# POWER.net
KiCad netlist of a schematic drawn in Altium Designer
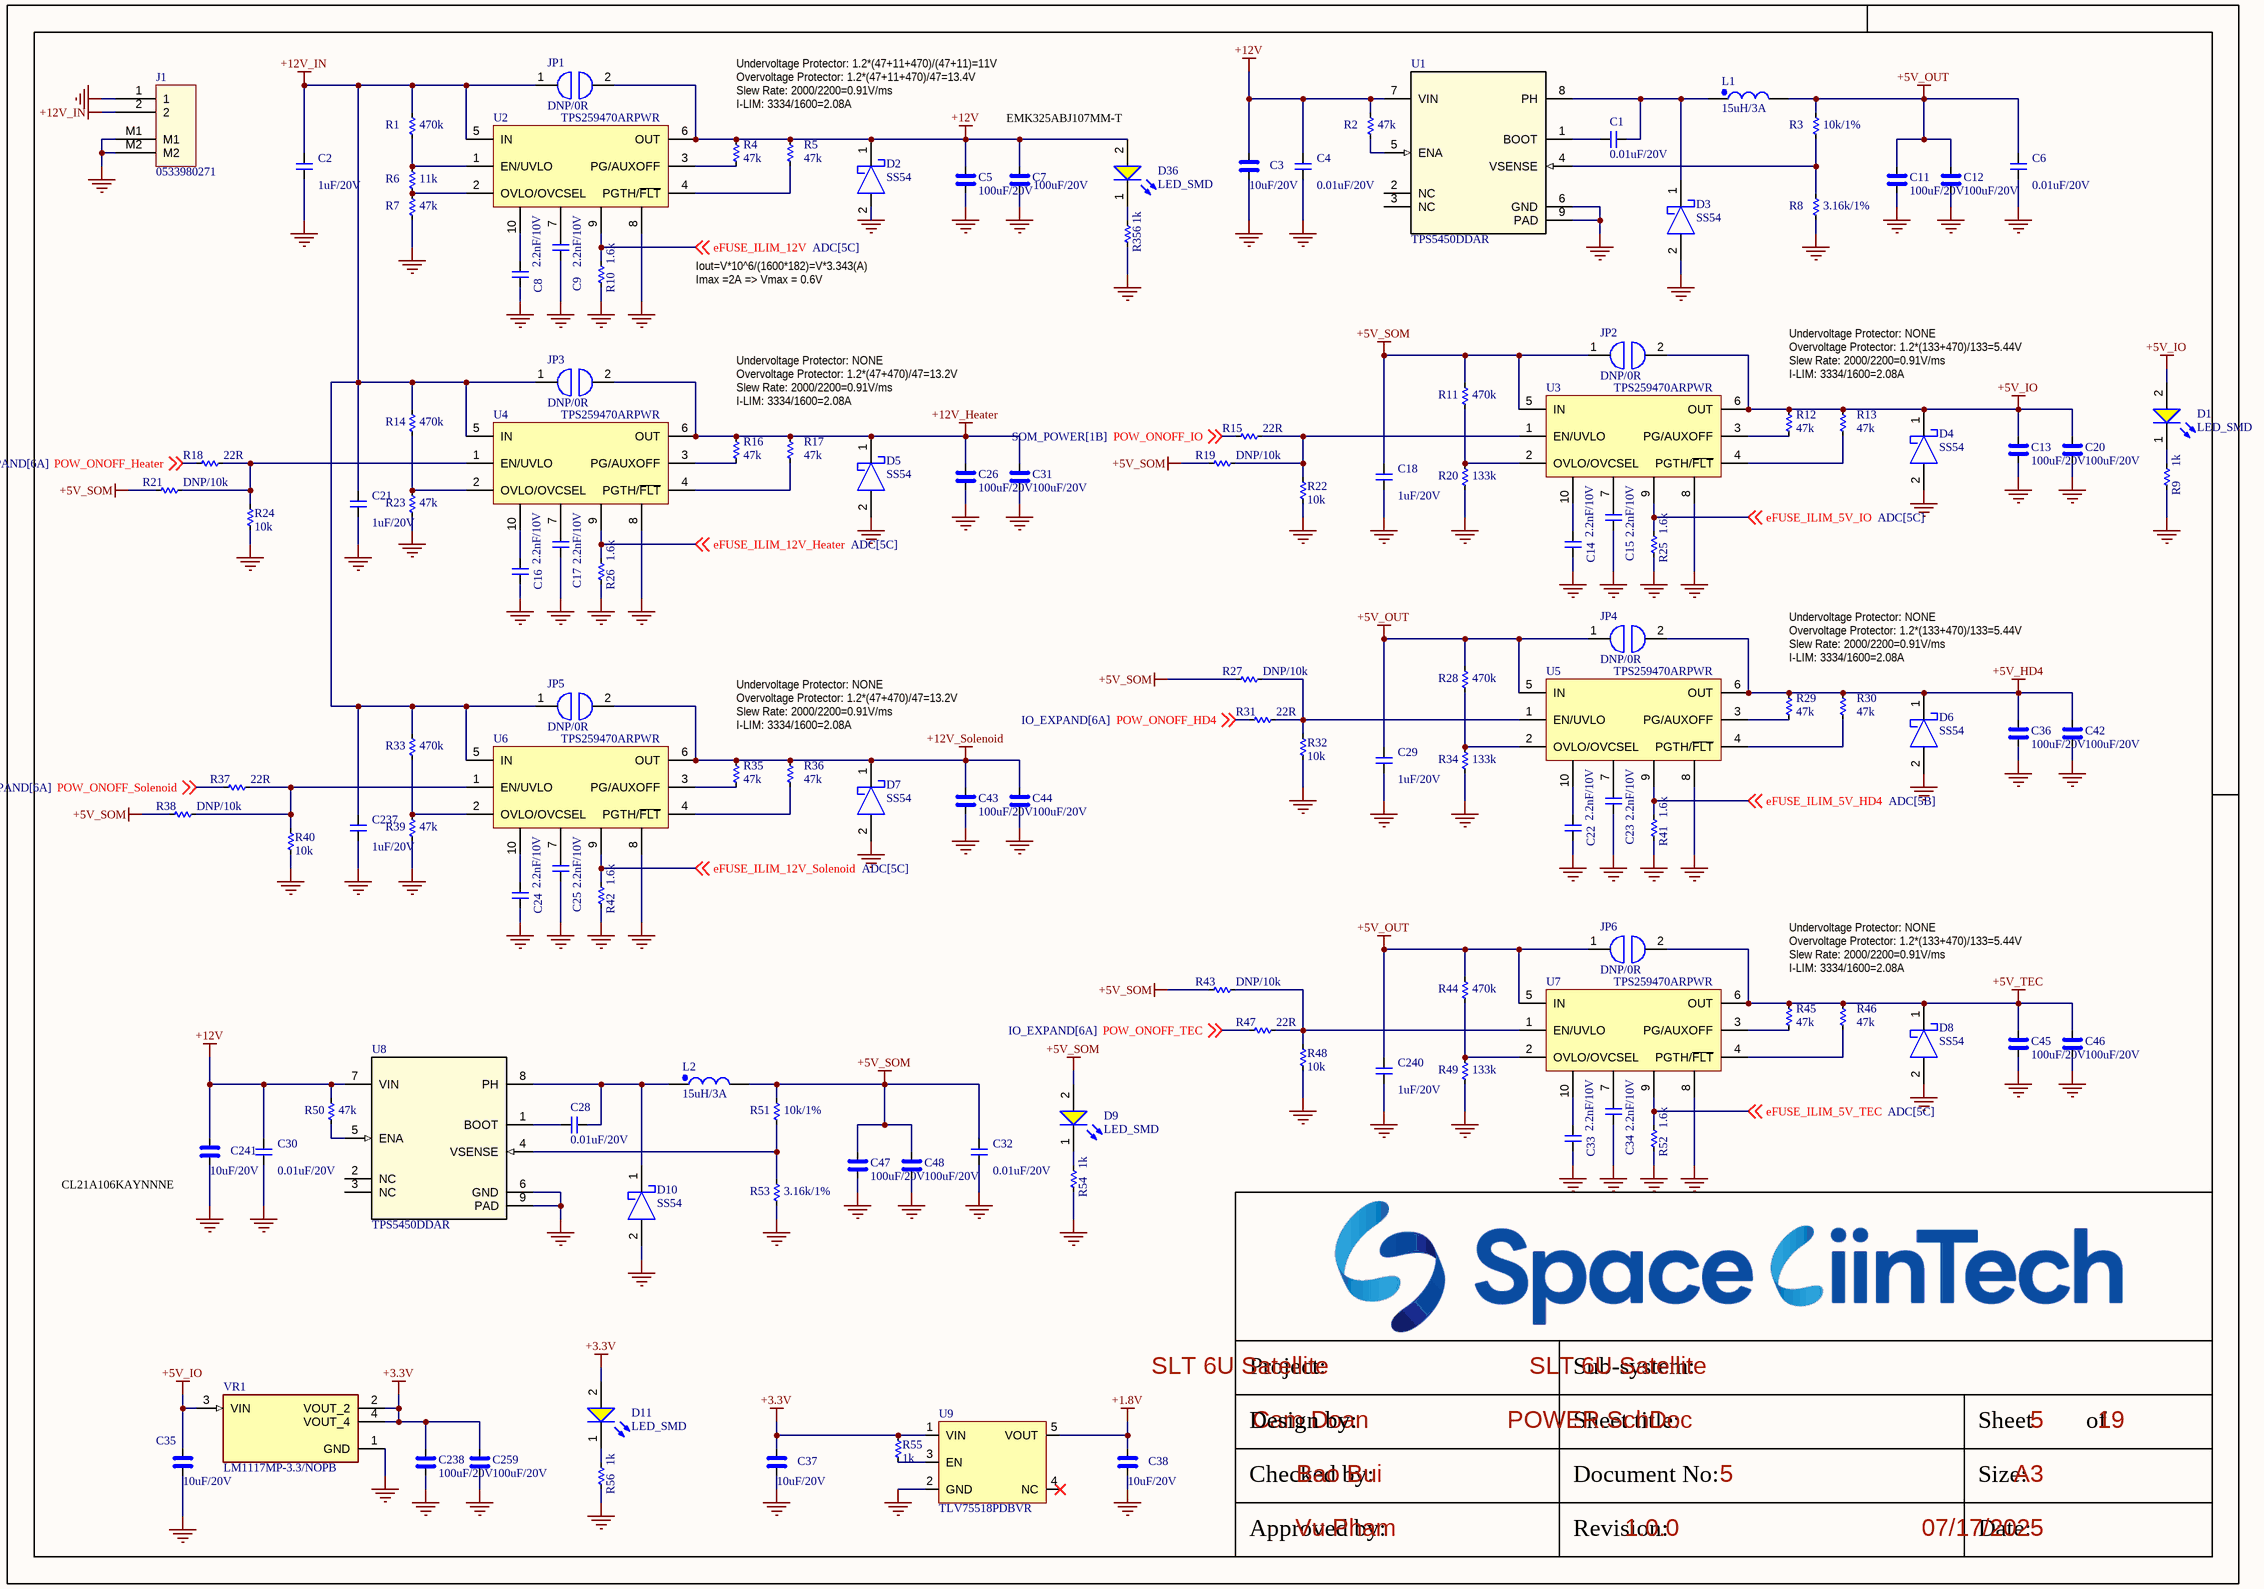
[diagram p0: POWER.SchDoc]

(export (version "E")
  (design (tool "Eeschema 10.0.6"))
  (components
    (comp (ref "C1")
      (value "0.01uF/20V")
      (footprint "CAP_C_1005X60")
      (description "CAP CHIP")
      (libsource (lib "LABLIB") (part "_CAP_C_2"))
    )
    (comp (ref "C2")
      (value "1uF/20V")
      (footprint "CAP_C_1005X60")
      (description "CAP CHIP")
      (libsource (lib "LABLIB") (part "_CAP_C_2"))
    )
    (comp (ref "C3")
      (value "10uF/20V")
      (footprint "CAP_C_2012X110")
      (description "CAP CHIP High Value")
      (libsource (lib "LABLIB") (part "_CAP_C_High_2"))
    )
    (comp (ref "C4")
      (value "0.01uF/20V")
      (footprint "CAP_C_1005X60")
      (description "CAP CHIP")
      (libsource (lib "LABLIB") (part "_CAP_C_2"))
    )
    (comp (ref "C5")
      (value "100uF/20V")
      (footprint "CAP_C_3225X80")
      (description "CAP CHIP High Value")
      (libsource (lib "LABLIB") (part "_CAP_C_High_2"))
    )
    (comp (ref "C6")
      (value "0.01uF/20V")
      (footprint "CAP_C_1005X60")
      (description "CAP CHIP")
      (libsource (lib "LABLIB") (part "_CAP_C_2"))
    )
    (comp (ref "C7")
      (value "100uF/20V")
      (footprint "CAP_C_3225X80")
      (description "CAP CHIP High Value")
      (libsource (lib "LABLIB") (part "_CAP_C_High_2"))
    )
    (comp (ref "C8")
      (value "2.2nF/10V")
      (footprint "CAP_C_1005X60")
      (description "CAP CHIP")
      (libsource (lib "LABLIB") (part "_CAP_C_2"))
    )
    (comp (ref "C9")
      (value "2.2nF/10V")
      (footprint "CAP_C_1005X60")
      (description "CAP CHIP")
      (libsource (lib "LABLIB") (part "_CAP_C_2"))
    )
    (comp (ref "C11")
      (value "100uF/20V")
      (footprint "CAP_C_3225X80")
      (description "CAP CHIP High Value")
      (libsource (lib "LABLIB") (part "_CAP_C_High_2"))
    )
    (comp (ref "C12")
      (value "100uF/20V")
      (footprint "CAP_C_3225X80")
      (description "CAP CHIP High Value")
      (libsource (lib "LABLIB") (part "_CAP_C_High_2"))
    )
    (comp (ref "C13")
      (value "100uF/20V")
      (footprint "CAP_C_3225X80")
      (description "CAP CHIP High Value")
      (libsource (lib "LABLIB") (part "_CAP_C_High_2"))
    )
    (comp (ref "C14")
      (value "2.2nF/10V")
      (footprint "CAP_C_1005X60")
      (description "CAP CHIP")
      (libsource (lib "LABLIB") (part "_CAP_C_2"))
    )
    (comp (ref "C15")
      (value "2.2nF/10V")
      (footprint "CAP_C_1005X60")
      (description "CAP CHIP")
      (libsource (lib "LABLIB") (part "_CAP_C_2"))
    )
    (comp (ref "C16")
      (value "2.2nF/10V")
      (footprint "CAP_C_1005X60")
      (description "CAP CHIP")
      (libsource (lib "LABLIB") (part "_CAP_C_2"))
    )
    (comp (ref "C17")
      (value "2.2nF/10V")
      (footprint "CAP_C_1005X60")
      (description "CAP CHIP")
      (libsource (lib "LABLIB") (part "_CAP_C_2"))
    )
    (comp (ref "C18")
      (value "1uF/20V")
      (footprint "CAP_C_1005X60")
      (description "CAP CHIP")
      (libsource (lib "LABLIB") (part "_CAP_C_2"))
    )
    (comp (ref "C20")
      (value "100uF/20V")
      (footprint "CAP_C_3225X80")
      (description "CAP CHIP High Value")
      (libsource (lib "LABLIB") (part "_CAP_C_High_2"))
    )
    (comp (ref "C21")
      (value "1uF/20V")
      (footprint "CAP_C_1005X60")
      (description "CAP CHIP")
      (libsource (lib "LABLIB") (part "_CAP_C_2"))
    )
    (comp (ref "C22")
      (value "2.2nF/10V")
      (footprint "CAP_C_1005X60")
      (description "CAP CHIP")
      (libsource (lib "LABLIB") (part "_CAP_C_2"))
    )
    (comp (ref "C23")
      (value "2.2nF/10V")
      (footprint "CAP_C_1005X60")
      (description "CAP CHIP")
      (libsource (lib "LABLIB") (part "_CAP_C_2"))
    )
    (comp (ref "C24")
      (value "2.2nF/10V")
      (footprint "CAP_C_1005X60")
      (description "CAP CHIP")
      (libsource (lib "LABLIB") (part "_CAP_C_2"))
    )
    (comp (ref "C25")
      (value "2.2nF/10V")
      (footprint "CAP_C_1005X60")
      (description "CAP CHIP")
      (libsource (lib "LABLIB") (part "_CAP_C_2"))
    )
    (comp (ref "C26")
      (value "100uF/20V")
      (footprint "CAP_C_3225X80")
      (description "CAP CHIP High Value")
      (libsource (lib "LABLIB") (part "_CAP_C_High_2"))
    )
    (comp (ref "C28")
      (value "0.01uF/20V")
      (footprint "CAP_C_1005X60")
      (description "CAP CHIP")
      (libsource (lib "LABLIB") (part "_CAP_C_2"))
    )
    (comp (ref "C29")
      (value "1uF/20V")
      (footprint "CAP_C_1005X60")
      (description "CAP CHIP")
      (libsource (lib "LABLIB") (part "_CAP_C_2"))
    )
    (comp (ref "C30")
      (value "0.01uF/20V")
      (footprint "CAP_C_1005X60")
      (description "CAP CHIP")
      (libsource (lib "LABLIB") (part "_CAP_C_2"))
    )
    (comp (ref "C31")
      (value "100uF/20V")
      (footprint "CAP_C_3225X80")
      (description "CAP CHIP High Value")
      (libsource (lib "LABLIB") (part "_CAP_C_High_2"))
    )
    (comp (ref "C32")
      (value "0.01uF/20V")
      (footprint "CAP_C_1005X60")
      (description "CAP CHIP")
      (libsource (lib "LABLIB") (part "_CAP_C_2"))
    )
    (comp (ref "C33")
      (value "2.2nF/10V")
      (footprint "CAP_C_1005X60")
      (description "CAP CHIP")
      (libsource (lib "LABLIB") (part "_CAP_C_2"))
    )
    (comp (ref "C34")
      (value "2.2nF/10V")
      (footprint "CAP_C_1005X60")
      (description "CAP CHIP")
      (libsource (lib "LABLIB") (part "_CAP_C_2"))
    )
    (comp (ref "C35")
      (value "10uF/20V")
      (footprint "CAP_C_2012X110")
      (description "CAP CHIP High Value")
      (libsource (lib "LABLIB") (part "_CAP_C_High_2"))
    )
    (comp (ref "C36")
      (value "100uF/20V")
      (footprint "CAP_C_3225X80")
      (description "CAP CHIP High Value")
      (libsource (lib "LABLIB") (part "_CAP_C_High_2"))
    )
    (comp (ref "C37")
      (value "10uF/20V")
      (footprint "CAP_C_2012X110")
      (description "CAP CHIP High Value")
      (libsource (lib "LABLIB") (part "_CAP_C_High_2"))
    )
    (comp (ref "C38")
      (value "10uF/20V")
      (footprint "CAP_C_2012X110")
      (description "CAP CHIP High Value")
      (libsource (lib "LABLIB") (part "_CAP_C_High_2"))
    )
    (comp (ref "C42")
      (value "100uF/20V")
      (footprint "CAP_C_3225X80")
      (description "CAP CHIP High Value")
      (libsource (lib "LABLIB") (part "_CAP_C_High_2"))
    )
    (comp (ref "C43")
      (value "100uF/20V")
      (footprint "CAP_C_3225X80")
      (description "CAP CHIP High Value")
      (libsource (lib "LABLIB") (part "_CAP_C_High_2"))
    )
    (comp (ref "C44")
      (value "100uF/20V")
      (footprint "CAP_C_3225X80")
      (description "CAP CHIP High Value")
      (libsource (lib "LABLIB") (part "_CAP_C_High_2"))
    )
    (comp (ref "C45")
      (value "100uF/20V")
      (footprint "CAP_C_3225X80")
      (description "CAP CHIP High Value")
      (libsource (lib "LABLIB") (part "_CAP_C_High_2"))
    )
    (comp (ref "C46")
      (value "100uF/20V")
      (footprint "CAP_C_3225X80")
      (description "CAP CHIP High Value")
      (libsource (lib "LABLIB") (part "_CAP_C_High_2"))
    )
    (comp (ref "C47")
      (value "100uF/20V")
      (footprint "CAP_C_3225X80")
      (description "CAP CHIP High Value")
      (libsource (lib "LABLIB") (part "_CAP_C_High_2"))
    )
    (comp (ref "C48")
      (value "100uF/20V")
      (footprint "CAP_C_3225X80")
      (description "CAP CHIP High Value")
      (libsource (lib "LABLIB") (part "_CAP_C_High_2"))
    )
    (comp (ref "C237")
      (value "1uF/20V")
      (footprint "CAP_C_1005X60")
      (description "CAP CHIP")
      (libsource (lib "LABLIB") (part "_CAP_C_2"))
    )
    (comp (ref "C238")
      (value "100uF/20V")
      (footprint "CAP_C_3225X80")
      (description "CAP CHIP High Value")
      (libsource (lib "LABLIB") (part "_CAP_C_High_2"))
    )
    (comp (ref "C240")
      (value "1uF/20V")
      (footprint "CAP_C_1005X60")
      (description "CAP CHIP")
      (libsource (lib "LABLIB") (part "_CAP_C_2"))
    )
    (comp (ref "C241")
      (value "10uF/20V")
      (footprint "CAP_C_2012X110")
      (description "CAP CHIP High Value")
      (libsource (lib "LABLIB") (part "_CAP_C_High_2"))
    )
    (comp (ref "C259")
      (value "100uF/20V")
      (footprint "CAP_C_3225X80")
      (description "CAP CHIP High Value")
      (libsource (lib "LABLIB") (part "_CAP_C_High_2"))
    )
    (comp (ref "D1") (value "LED_SMD") (footprint "LED_0603") (libsource (lib "LABLIB") (part "LED_SMD")))
    (comp (ref "D2")
      (value "SS54")
      (footprint "DO-214AC_SMA")
      (description "DIODE SCHOTTKY 60V 3A DO214AA")
      (libsource (lib "EXP_HW_V3") (part "SS54"))
    )
    (comp (ref "D3")
      (value "SS54")
      (footprint "DO-214AC_SMA")
      (description "DIODE SCHOTTKY 60V 3A DO214AA")
      (libsource (lib "EXP_HW_V3") (part "SS54"))
    )
    (comp (ref "D4")
      (value "SS54")
      (footprint "DO-214AC_SMA")
      (description "DIODE SCHOTTKY 60V 3A DO214AA")
      (libsource (lib "EXP_HW_V3") (part "SS54"))
    )
    (comp (ref "D5")
      (value "SS54")
      (footprint "DO-214AC_SMA")
      (description "DIODE SCHOTTKY 60V 3A DO214AA")
      (libsource (lib "EXP_HW_V3") (part "SS54"))
    )
    (comp (ref "D6")
      (value "SS54")
      (footprint "DO-214AC_SMA")
      (description "DIODE SCHOTTKY 60V 3A DO214AA")
      (libsource (lib "EXP_HW_V3") (part "SS54"))
    )
    (comp (ref "D7")
      (value "SS54")
      (footprint "DO-214AC_SMA")
      (description "DIODE SCHOTTKY 60V 3A DO214AA")
      (libsource (lib "EXP_HW_V3") (part "SS54"))
    )
    (comp (ref "D8")
      (value "SS54")
      (footprint "DO-214AC_SMA")
      (description "DIODE SCHOTTKY 60V 3A DO214AA")
      (libsource (lib "EXP_HW_V3") (part "SS54"))
    )
    (comp (ref "D9") (value "LED_SMD") (footprint "LED_0603") (libsource (lib "LABLIB") (part "LED_SMD")))
    (comp (ref "D10")
      (value "SS54")
      (footprint "DO-214AC_SMA")
      (description "DIODE SCHOTTKY 60V 3A DO214AA")
      (libsource (lib "EXP_HW_V3") (part "SS54"))
    )
    (comp (ref "D11") (value "LED_SMD") (footprint "LED_0603") (libsource (lib "LABLIB") (part "LED_SMD")))
    (comp (ref "D36") (value "LED_SMD") (footprint "LED_0603") (libsource (lib "LABLIB") (part "LED_SMD")))
    (comp (ref "J1")
      (value "0533980271")
      (footprint "MOLEX_0533980271")
      (libsource (lib "LABLIB") (part "Header 2x1_2M"))
    )
    (comp (ref "JP1") (value "DNP/0R") (footprint "RES_C_1608X60") (libsource (lib "EXP_V1") (part "JUMPER")))
    (comp (ref "JP2") (value "DNP/0R") (footprint "RES_C_1608X60") (libsource (lib "EXP_V1") (part "JUMPER")))
    (comp (ref "JP3") (value "DNP/0R") (footprint "RES_C_1608X60") (libsource (lib "EXP_V1") (part "JUMPER")))
    (comp (ref "JP4") (value "DNP/0R") (footprint "RES_C_1608X60") (libsource (lib "EXP_V1") (part "JUMPER")))
    (comp (ref "JP5") (value "DNP/0R") (footprint "RES_C_1608X60") (libsource (lib "EXP_V1") (part "JUMPER")))
    (comp (ref "JP6") (value "DNP/0R") (footprint "RES_C_1608X60") (libsource (lib "EXP_V1") (part "JUMPER")))
    (comp (ref "L1")
      (value "15uH/3A")
      (footprint "IND730660x480")
      (description "SRP7050TA-100M")
      (libsource (lib "LABLIB") (part "_IND"))
    )
    (comp (ref "L2")
      (value "15uH/3A")
      (footprint "IND730660x480")
      (description "SRP7050TA-100M")
      (libsource (lib "LABLIB") (part "_IND"))
    )
    (comp (ref "R1")
      (value "470k")
      (footprint "RES_C_1005X40")
      (description "RES")
      (libsource (lib "LABLIB") (part "_RES_B_2"))
    )
    (comp (ref "R2")
      (value "47k")
      (footprint "RES_C_1005X40")
      (description "RES")
      (libsource (lib "LABLIB") (part "_RES_B_2"))
    )
    (comp (ref "R3")
      (value "10k/1%")
      (footprint "RES_C_1005X40")
      (description "RES")
      (libsource (lib "LABLIB") (part "_RES_B_2"))
    )
    (comp (ref "R4")
      (value "47k")
      (footprint "RES_C_1005X40")
      (description "RES")
      (libsource (lib "LABLIB") (part "_RES_B_2"))
    )
    (comp (ref "R5")
      (value "47k")
      (footprint "RES_C_1005X40")
      (description "RES")
      (libsource (lib "LABLIB") (part "_RES_B_2"))
    )
    (comp (ref "R6")
      (value "11k")
      (footprint "RES_C_1005X40")
      (description "RES")
      (libsource (lib "LABLIB") (part "_RES_B_2"))
    )
    (comp (ref "R7")
      (value "47k")
      (footprint "RES_C_1005X40")
      (description "RES")
      (libsource (lib "LABLIB") (part "_RES_B_2"))
    )
    (comp (ref "R8")
      (value "3.16k/1%")
      (footprint "RES_C_1005X40")
      (description "RES")
      (libsource (lib "LABLIB") (part "_RES_B_2"))
    )
    (comp (ref "R9")
      (value "1k")
      (footprint "RES_C_1005X40")
      (description "RES")
      (libsource (lib "LABLIB") (part "_RES_B_2"))
    )
    (comp (ref "R10")
      (value "1.6k")
      (footprint "RES_C_1005X40")
      (description "RES")
      (libsource (lib "LABLIB") (part "_RES_B_2"))
    )
    (comp (ref "R11")
      (value "470k")
      (footprint "RES_C_1005X40")
      (description "RES")
      (libsource (lib "LABLIB") (part "_RES_B_2"))
    )
    (comp (ref "R12")
      (value "47k")
      (footprint "RES_C_1005X40")
      (description "RES")
      (libsource (lib "LABLIB") (part "_RES_B_2"))
    )
    (comp (ref "R13")
      (value "47k")
      (footprint "RES_C_1005X40")
      (description "RES")
      (libsource (lib "LABLIB") (part "_RES_B_2"))
    )
    (comp (ref "R14")
      (value "470k")
      (footprint "RES_C_1005X40")
      (description "RES")
      (libsource (lib "LABLIB") (part "_RES_B_2"))
    )
    (comp (ref "R15")
      (value "22R")
      (footprint "RES_C_1005X40")
      (description "RES")
      (libsource (lib "LABLIB") (part "_RES_B_2"))
    )
    (comp (ref "R16")
      (value "47k")
      (footprint "RES_C_1005X40")
      (description "RES")
      (libsource (lib "LABLIB") (part "_RES_B_2"))
    )
    (comp (ref "R17")
      (value "47k")
      (footprint "RES_C_1005X40")
      (description "RES")
      (libsource (lib "LABLIB") (part "_RES_B_2"))
    )
    (comp (ref "R18")
      (value "22R")
      (footprint "RES_C_1005X40")
      (description "RES")
      (libsource (lib "LABLIB") (part "_RES_B_2"))
    )
    (comp (ref "R19")
      (value "DNP/10k")
      (footprint "RES_C_1005X40")
      (description "RES")
      (libsource (lib "LABLIB") (part "_RES_B_2"))
    )
    (comp (ref "R20")
      (value "133k")
      (footprint "RES_C_1005X40")
      (description "RES")
      (libsource (lib "LABLIB") (part "_RES_B_2"))
    )
    (comp (ref "R21")
      (value "DNP/10k")
      (footprint "RES_C_1005X40")
      (description "RES")
      (libsource (lib "LABLIB") (part "_RES_B_2"))
    )
    (comp (ref "R22")
      (value "10k")
      (footprint "RES_C_1005X40")
      (description "RES")
      (libsource (lib "LABLIB") (part "_RES_B_2"))
    )
    (comp (ref "R23")
      (value "47k")
      (footprint "RES_C_1005X40")
      (description "RES")
      (libsource (lib "LABLIB") (part "_RES_B_2"))
    )
    (comp (ref "R24")
      (value "10k")
      (footprint "RES_C_1005X40")
      (description "RES")
      (libsource (lib "LABLIB") (part "_RES_B_2"))
    )
    (comp (ref "R25")
      (value "1.6k")
      (footprint "RES_C_1005X40")
      (description "RES")
      (libsource (lib "LABLIB") (part "_RES_B_2"))
    )
    (comp (ref "R26")
      (value "1.6k")
      (footprint "RES_C_1005X40")
      (description "RES")
      (libsource (lib "LABLIB") (part "_RES_B_2"))
    )
    (comp (ref "R27")
      (value "DNP/10k")
      (footprint "RES_C_1005X40")
      (description "RES")
      (libsource (lib "LABLIB") (part "_RES_B_2"))
    )
    (comp (ref "R28")
      (value "470k")
      (footprint "RES_C_1005X40")
      (description "RES")
      (libsource (lib "LABLIB") (part "_RES_B_2"))
    )
    (comp (ref "R29")
      (value "47k")
      (footprint "RES_C_1005X40")
      (description "RES")
      (libsource (lib "LABLIB") (part "_RES_B_2"))
    )
    (comp (ref "R30")
      (value "47k")
      (footprint "RES_C_1005X40")
      (description "RES")
      (libsource (lib "LABLIB") (part "_RES_B_2"))
    )
    (comp (ref "R31")
      (value "22R")
      (footprint "RES_C_1005X40")
      (description "RES")
      (libsource (lib "LABLIB") (part "_RES_B_2"))
    )
    (comp (ref "R32")
      (value "10k")
      (footprint "RES_C_1005X40")
      (description "RES")
      (libsource (lib "LABLIB") (part "_RES_B_2"))
    )
    (comp (ref "R33")
      (value "470k")
      (footprint "RES_C_1005X40")
      (description "RES")
      (libsource (lib "LABLIB") (part "_RES_B_2"))
    )
    (comp (ref "R34")
      (value "133k")
      (footprint "RES_C_1005X40")
      (description "RES")
      (libsource (lib "LABLIB") (part "_RES_B_2"))
    )
    (comp (ref "R35")
      (value "47k")
      (footprint "RES_C_1005X40")
      (description "RES")
      (libsource (lib "LABLIB") (part "_RES_B_2"))
    )
    (comp (ref "R36")
      (value "47k")
      (footprint "RES_C_1005X40")
      (description "RES")
      (libsource (lib "LABLIB") (part "_RES_B_2"))
    )
    (comp (ref "R37")
      (value "22R")
      (footprint "RES_C_1005X40")
      (description "RES")
      (libsource (lib "LABLIB") (part "_RES_B_2"))
    )
    (comp (ref "R38")
      (value "DNP/10k")
      (footprint "RES_C_1005X40")
      (description "RES")
      (libsource (lib "LABLIB") (part "_RES_B_2"))
    )
    (comp (ref "R39")
      (value "47k")
      (footprint "RES_C_1005X40")
      (description "RES")
      (libsource (lib "LABLIB") (part "_RES_B_2"))
    )
    (comp (ref "R40")
      (value "10k")
      (footprint "RES_C_1005X40")
      (description "RES")
      (libsource (lib "LABLIB") (part "_RES_B_2"))
    )
    (comp (ref "R41")
      (value "1.6k")
      (footprint "RES_C_1005X40")
      (description "RES")
      (libsource (lib "LABLIB") (part "_RES_B_2"))
    )
    (comp (ref "R42")
      (value "1.6k")
      (footprint "RES_C_1005X40")
      (description "RES")
      (libsource (lib "LABLIB") (part "_RES_B_2"))
    )
    (comp (ref "R43")
      (value "DNP/10k")
      (footprint "RES_C_1005X40")
      (description "RES")
      (libsource (lib "LABLIB") (part "_RES_B_2"))
    )
    (comp (ref "R44")
      (value "470k")
      (footprint "RES_C_1005X40")
      (description "RES")
      (libsource (lib "LABLIB") (part "_RES_B_2"))
    )
    (comp (ref "R45")
      (value "47k")
      (footprint "RES_C_1005X40")
      (description "RES")
      (libsource (lib "LABLIB") (part "_RES_B_2"))
    )
    (comp (ref "R46")
      (value "47k")
      (footprint "RES_C_1005X40")
      (description "RES")
      (libsource (lib "LABLIB") (part "_RES_B_2"))
    )
    (comp (ref "R47")
      (value "22R")
      (footprint "RES_C_1005X40")
      (description "RES")
      (libsource (lib "LABLIB") (part "_RES_B_2"))
    )
    (comp (ref "R48")
      (value "10k")
      (footprint "RES_C_1005X40")
      (description "RES")
      (libsource (lib "LABLIB") (part "_RES_B_2"))
    )
    (comp (ref "R49")
      (value "133k")
      (footprint "RES_C_1005X40")
      (description "RES")
      (libsource (lib "LABLIB") (part "_RES_B_2"))
    )
    (comp (ref "R50")
      (value "47k")
      (footprint "RES_C_1005X40")
      (description "RES")
      (libsource (lib "LABLIB") (part "_RES_B_2"))
    )
    (comp (ref "R51")
      (value "10k/1%")
      (footprint "RES_C_1005X40")
      (description "RES")
      (libsource (lib "LABLIB") (part "_RES_B_2"))
    )
    (comp (ref "R52")
      (value "1.6k")
      (footprint "RES_C_1005X40")
      (description "RES")
      (libsource (lib "LABLIB") (part "_RES_B_2"))
    )
    (comp (ref "R53")
      (value "3.16k/1%")
      (footprint "RES_C_1005X40")
      (description "RES")
      (libsource (lib "LABLIB") (part "_RES_B_2"))
    )
    (comp (ref "R54")
      (value "1k")
      (footprint "RES_C_1005X40")
      (description "RES")
      (libsource (lib "LABLIB") (part "_RES_B_2"))
    )
    (comp (ref "R55")
      (value "1k")
      (footprint "RES_C_1005X40")
      (description "RES")
      (libsource (lib "LABLIB") (part "_RES_B_2"))
    )
    (comp (ref "R56")
      (value "1k")
      (footprint "RES_C_1005X40")
      (description "RES")
      (libsource (lib "LABLIB") (part "_RES_B_2"))
    )
    (comp (ref "R356")
      (value "1k")
      (footprint "RES_C_1005X40")
      (description "RES")
      (libsource (lib "LABLIB") (part "_RES_B_2"))
    )
    (comp (ref "U1")
      (value "TPS5450DDAR")
      (footprint "DDA0008J")
      (description "No Description Available")
      (libsource (lib "new_component") (part "TPS5430DDAR"))
    )
    (comp (ref "U2")
      (value "TPS259470ARPWR")
      (footprint "VQFN-HR-10")
      (libsource (lib "EXP_HW_V3") (part "TPS259470ARPWR"))
    )
    (comp (ref "U3")
      (value "TPS259470ARPWR")
      (footprint "VQFN-HR-10")
      (libsource (lib "EXP_HW_V3") (part "TPS259470ARPWR"))
    )
    (comp (ref "U4")
      (value "TPS259470ARPWR")
      (footprint "VQFN-HR-10")
      (libsource (lib "EXP_HW_V3") (part "TPS259470ARPWR"))
    )
    (comp (ref "U5")
      (value "TPS259470ARPWR")
      (footprint "VQFN-HR-10")
      (libsource (lib "EXP_HW_V3") (part "TPS259470ARPWR"))
    )
    (comp (ref "U6")
      (value "TPS259470ARPWR")
      (footprint "VQFN-HR-10")
      (libsource (lib "EXP_HW_V3") (part "TPS259470ARPWR"))
    )
    (comp (ref "U7")
      (value "TPS259470ARPWR")
      (footprint "VQFN-HR-10")
      (libsource (lib "EXP_HW_V3") (part "TPS259470ARPWR"))
    )
    (comp (ref "U8")
      (value "TPS5450DDAR")
      (footprint "DDA0008J")
      (description "No Description Available")
      (libsource (lib "new_component") (part "TPS5430DDAR"))
    )
    (comp (ref "U9")
      (value "TLV75518PDBVR")
      (footprint "SOT25")
      (libsource (lib "CAMERA_SchLib") (part "IC_POWER_AP7347DQ"))
    )
    (comp (ref "VR1")
      (value "LM1117MP-3.3/NOPB")
      (footprint "VREG_LM1117MP-3.3/NOPB")
      (description "800-mA 15-V linear voltage regulator")
      (fields (field (name "MF") "Texas Instruments"))
      (libsource (lib "new_component") (part "LM1117MP-3.3/NOPB"))
    )
  )
  (nets
    (net (code "1") (name "+1.8V") (class "Default")
      (node (ref "C38") (pin "1") (pinfunction "1_1") (pintype "passive"))
      (node (ref "U9") (pin "5") (pinfunction "VOUT_5") (pintype "passive"))
    )
    (net (code "2") (name "+3.3V") (class "Default")
      (node (ref "C238") (pin "2") (pinfunction "2_2") (pintype "passive"))
      (node (ref "C259") (pin "2") (pinfunction "2_2") (pintype "passive"))
      (node (ref "C37") (pin "1") (pinfunction "1_1") (pintype "passive"))
      (node (ref "D11") (pin "2") (pinfunction "A_2") (pintype "passive"))
      (node (ref "R55") (pin "2") (pinfunction "2_2") (pintype "passive"))
      (node (ref "U9") (pin "1") (pinfunction "VIN_1") (pintype "passive"))
      (node (ref "VR1") (pin "2") (pinfunction "VOUT_2_2") (pintype "power_in"))
      (node (ref "VR1") (pin "4") (pinfunction "VOUT_4_4") (pintype "power_in"))
    )
    (net (code "3") (name "+5V_HD4") (class "Default")
      (node (ref "C36") (pin "2") (pinfunction "2_2") (pintype "passive"))
      (node (ref "C42") (pin "2") (pinfunction "2_2") (pintype "passive"))
      (node (ref "D6") (pin "1") (pinfunction "1_1") (pintype "passive"))
      (node (ref "JP4") (pin "2") (pinfunction "2_2") (pintype "passive"))
      (node (ref "R29") (pin "2") (pinfunction "2_2") (pintype "passive"))
      (node (ref "R30") (pin "2") (pinfunction "2_2") (pintype "passive"))
      (node (ref "U5") (pin "6") (pinfunction "OUT_6") (pintype "passive"))
    )
    (net (code "4") (name "+5V_IO") (class "Default")
      (node (ref "C13") (pin "2") (pinfunction "2_2") (pintype "passive"))
      (node (ref "C20") (pin "2") (pinfunction "2_2") (pintype "passive"))
      (node (ref "C35") (pin "1") (pinfunction "1_1") (pintype "passive"))
      (node (ref "D1") (pin "2") (pinfunction "A_2") (pintype "passive"))
      (node (ref "D4") (pin "1") (pinfunction "1_1") (pintype "passive"))
      (node (ref "JP2") (pin "2") (pinfunction "2_2") (pintype "passive"))
      (node (ref "R12") (pin "2") (pinfunction "2_2") (pintype "passive"))
      (node (ref "R13") (pin "2") (pinfunction "2_2") (pintype "passive"))
      (node (ref "U3") (pin "6") (pinfunction "OUT_6") (pintype "passive"))
      (node (ref "VR1") (pin "3") (pinfunction "VIN_3") (pintype "input"))
    )
    (net (code "5") (name "+5V_OUT") (class "Default")
      (node (ref "C11") (pin "2") (pinfunction "2_2") (pintype "passive"))
      (node (ref "C12") (pin "2") (pinfunction "2_2") (pintype "passive"))
      (node (ref "C240") (pin "2") (pinfunction "2_2") (pintype "passive"))
      (node (ref "C29") (pin "2") (pinfunction "2_2") (pintype "passive"))
      (node (ref "C6") (pin "2") (pinfunction "2_2") (pintype "passive"))
      (node (ref "JP4") (pin "1") (pinfunction "1_1") (pintype "passive"))
      (node (ref "JP6") (pin "1") (pinfunction "1_1") (pintype "passive"))
      (node (ref "L1") (pin "2") (pinfunction "2_2") (pintype "passive"))
      (node (ref "R28") (pin "2") (pinfunction "2_2") (pintype "passive"))
      (node (ref "R3") (pin "2") (pinfunction "2_2") (pintype "passive"))
      (node (ref "R44") (pin "2") (pinfunction "2_2") (pintype "passive"))
      (node (ref "U5") (pin "5") (pinfunction "IN_5") (pintype "passive"))
      (node (ref "U7") (pin "5") (pinfunction "IN_5") (pintype "passive"))
    )
    (net (code "6") (name "+5V_SOM") (class "Default")
      (node (ref "C18") (pin "2") (pinfunction "2_2") (pintype "passive"))
      (node (ref "C32") (pin "2") (pinfunction "2_2") (pintype "passive"))
      (node (ref "C47") (pin "2") (pinfunction "2_2") (pintype "passive"))
      (node (ref "C48") (pin "2") (pinfunction "2_2") (pintype "passive"))
      (node (ref "D9") (pin "2") (pinfunction "A_2") (pintype "passive"))
      (node (ref "JP2") (pin "1") (pinfunction "1_1") (pintype "passive"))
      (node (ref "L2") (pin "2") (pinfunction "2_2") (pintype "passive"))
      (node (ref "R11") (pin "2") (pinfunction "2_2") (pintype "passive"))
      (node (ref "R19") (pin "2") (pinfunction "2_2") (pintype "passive"))
      (node (ref "R21") (pin "2") (pinfunction "2_2") (pintype "passive"))
      (node (ref "R27") (pin "2") (pinfunction "2_2") (pintype "passive"))
      (node (ref "R38") (pin "2") (pinfunction "2_2") (pintype "passive"))
      (node (ref "R43") (pin "2") (pinfunction "2_2") (pintype "passive"))
      (node (ref "R51") (pin "2") (pinfunction "2_2") (pintype "passive"))
      (node (ref "U3") (pin "5") (pinfunction "IN_5") (pintype "passive"))
    )
    (net (code "7") (name "+5V_TEC") (class "Default")
      (node (ref "C45") (pin "2") (pinfunction "2_2") (pintype "passive"))
      (node (ref "C46") (pin "2") (pinfunction "2_2") (pintype "passive"))
      (node (ref "D8") (pin "1") (pinfunction "1_1") (pintype "passive"))
      (node (ref "JP6") (pin "2") (pinfunction "2_2") (pintype "passive"))
      (node (ref "R45") (pin "2") (pinfunction "2_2") (pintype "passive"))
      (node (ref "R46") (pin "2") (pinfunction "2_2") (pintype "passive"))
      (node (ref "U7") (pin "6") (pinfunction "OUT_6") (pintype "passive"))
    )
    (net (code "8") (name "+12V") (class "Default")
      (node (ref "C241") (pin "1") (pinfunction "1_1") (pintype "passive"))
      (node (ref "C3") (pin "1") (pinfunction "1_1") (pintype "passive"))
      (node (ref "C30") (pin "2") (pinfunction "2_2") (pintype "passive"))
      (node (ref "C4") (pin "2") (pinfunction "2_2") (pintype "passive"))
      (node (ref "C5") (pin "2") (pinfunction "2_2") (pintype "passive"))
      (node (ref "C7") (pin "2") (pinfunction "2_2") (pintype "passive"))
      (node (ref "D2") (pin "1") (pinfunction "1_1") (pintype "passive"))
      (node (ref "D36") (pin "2") (pinfunction "A_2") (pintype "passive"))
      (node (ref "JP1") (pin "2") (pinfunction "2_2") (pintype "passive"))
      (node (ref "R2") (pin "2") (pinfunction "2_2") (pintype "passive"))
      (node (ref "R4") (pin "2") (pinfunction "2_2") (pintype "passive"))
      (node (ref "R5") (pin "2") (pinfunction "2_2") (pintype "passive"))
      (node (ref "R50") (pin "2") (pinfunction "2_2") (pintype "passive"))
      (node (ref "U1") (pin "7") (pinfunction "VIN_7") (pintype "power_in"))
      (node (ref "U2") (pin "6") (pinfunction "OUT_6") (pintype "passive"))
      (node (ref "U8") (pin "7") (pinfunction "VIN_7") (pintype "power_in"))
    )
    (net (code "9") (name "+12V_Heater") (class "Default")
      (node (ref "C26") (pin "2") (pinfunction "2_2") (pintype "passive"))
      (node (ref "C31") (pin "2") (pinfunction "2_2") (pintype "passive"))
      (node (ref "D5") (pin "1") (pinfunction "1_1") (pintype "passive"))
      (node (ref "JP3") (pin "2") (pinfunction "2_2") (pintype "passive"))
      (node (ref "R16") (pin "2") (pinfunction "2_2") (pintype "passive"))
      (node (ref "R17") (pin "2") (pinfunction "2_2") (pintype "passive"))
      (node (ref "U4") (pin "6") (pinfunction "OUT_6") (pintype "passive"))
    )
    (net (code "10") (name "+12V_IN") (class "Default")
      (node (ref "C2") (pin "2") (pinfunction "2_2") (pintype "passive"))
      (node (ref "C21") (pin "2") (pinfunction "2_2") (pintype "passive"))
      (node (ref "C237") (pin "2") (pinfunction "2_2") (pintype "passive"))
      (node (ref "J1") (pin "2") (pinfunction "2_2") (pintype "passive"))
      (node (ref "JP1") (pin "1") (pinfunction "1_1") (pintype "passive"))
      (node (ref "JP3") (pin "1") (pinfunction "1_1") (pintype "passive"))
      (node (ref "JP5") (pin "1") (pinfunction "1_1") (pintype "passive"))
      (node (ref "R1") (pin "2") (pinfunction "2_2") (pintype "passive"))
      (node (ref "R14") (pin "2") (pinfunction "2_2") (pintype "passive"))
      (node (ref "R33") (pin "2") (pinfunction "2_2") (pintype "passive"))
      (node (ref "U2") (pin "5") (pinfunction "IN_5") (pintype "passive"))
      (node (ref "U4") (pin "5") (pinfunction "IN_5") (pintype "passive"))
      (node (ref "U6") (pin "5") (pinfunction "IN_5") (pintype "passive"))
    )
    (net (code "11") (name "+12V_Solenoid") (class "Default")
      (node (ref "C43") (pin "2") (pinfunction "2_2") (pintype "passive"))
      (node (ref "C44") (pin "2") (pinfunction "2_2") (pintype "passive"))
      (node (ref "D7") (pin "1") (pinfunction "1_1") (pintype "passive"))
      (node (ref "JP5") (pin "2") (pinfunction "2_2") (pintype "passive"))
      (node (ref "R35") (pin "2") (pinfunction "2_2") (pintype "passive"))
      (node (ref "R36") (pin "2") (pinfunction "2_2") (pintype "passive"))
      (node (ref "U6") (pin "6") (pinfunction "OUT_6") (pintype "passive"))
    )
    (net (code "12") (name "GND") (class "Default")
      (node (ref "C11") (pin "1") (pinfunction "1_1") (pintype "passive"))
      (node (ref "C12") (pin "1") (pinfunction "1_1") (pintype "passive"))
      (node (ref "C13") (pin "1") (pinfunction "1_1") (pintype "passive"))
      (node (ref "C14") (pin "1") (pinfunction "1_1") (pintype "passive"))
      (node (ref "C15") (pin "1") (pinfunction "1_1") (pintype "passive"))
      (node (ref "C16") (pin "1") (pinfunction "1_1") (pintype "passive"))
      (node (ref "C17") (pin "1") (pinfunction "1_1") (pintype "passive"))
      (node (ref "C18") (pin "1") (pinfunction "1_1") (pintype "passive"))
      (node (ref "C2") (pin "1") (pinfunction "1_1") (pintype "passive"))
      (node (ref "C20") (pin "1") (pinfunction "1_1") (pintype "passive"))
      (node (ref "C21") (pin "1") (pinfunction "1_1") (pintype "passive"))
      (node (ref "C22") (pin "1") (pinfunction "1_1") (pintype "passive"))
      (node (ref "C23") (pin "1") (pinfunction "1_1") (pintype "passive"))
      (node (ref "C237") (pin "1") (pinfunction "1_1") (pintype "passive"))
      (node (ref "C238") (pin "1") (pinfunction "1_1") (pintype "passive"))
      (node (ref "C24") (pin "1") (pinfunction "1_1") (pintype "passive"))
      (node (ref "C240") (pin "1") (pinfunction "1_1") (pintype "passive"))
      (node (ref "C241") (pin "2") (pinfunction "2_2") (pintype "passive"))
      (node (ref "C25") (pin "1") (pinfunction "1_1") (pintype "passive"))
      (node (ref "C259") (pin "1") (pinfunction "1_1") (pintype "passive"))
      (node (ref "C26") (pin "1") (pinfunction "1_1") (pintype "passive"))
      (node (ref "C29") (pin "1") (pinfunction "1_1") (pintype "passive"))
      (node (ref "C3") (pin "2") (pinfunction "2_2") (pintype "passive"))
      (node (ref "C30") (pin "1") (pinfunction "1_1") (pintype "passive"))
      (node (ref "C31") (pin "1") (pinfunction "1_1") (pintype "passive"))
      (node (ref "C32") (pin "1") (pinfunction "1_1") (pintype "passive"))
      (node (ref "C33") (pin "1") (pinfunction "1_1") (pintype "passive"))
      (node (ref "C34") (pin "1") (pinfunction "1_1") (pintype "passive"))
      (node (ref "C35") (pin "2") (pinfunction "2_2") (pintype "passive"))
      (node (ref "C36") (pin "1") (pinfunction "1_1") (pintype "passive"))
      (node (ref "C37") (pin "2") (pinfunction "2_2") (pintype "passive"))
      (node (ref "C38") (pin "2") (pinfunction "2_2") (pintype "passive"))
      (node (ref "C4") (pin "1") (pinfunction "1_1") (pintype "passive"))
      (node (ref "C42") (pin "1") (pinfunction "1_1") (pintype "passive"))
      (node (ref "C43") (pin "1") (pinfunction "1_1") (pintype "passive"))
      (node (ref "C44") (pin "1") (pinfunction "1_1") (pintype "passive"))
      (node (ref "C45") (pin "1") (pinfunction "1_1") (pintype "passive"))
      (node (ref "C46") (pin "1") (pinfunction "1_1") (pintype "passive"))
      (node (ref "C47") (pin "1") (pinfunction "1_1") (pintype "passive"))
      (node (ref "C48") (pin "1") (pinfunction "1_1") (pintype "passive"))
      (node (ref "C5") (pin "1") (pinfunction "1_1") (pintype "passive"))
      (node (ref "C6") (pin "1") (pinfunction "1_1") (pintype "passive"))
      (node (ref "C7") (pin "1") (pinfunction "1_1") (pintype "passive"))
      (node (ref "C8") (pin "1") (pinfunction "1_1") (pintype "passive"))
      (node (ref "C9") (pin "1") (pinfunction "1_1") (pintype "passive"))
      (node (ref "D10") (pin "2") (pinfunction "2_2") (pintype "passive"))
      (node (ref "D2") (pin "2") (pinfunction "2_2") (pintype "passive"))
      (node (ref "D3") (pin "2") (pinfunction "2_2") (pintype "passive"))
      (node (ref "D4") (pin "2") (pinfunction "2_2") (pintype "passive"))
      (node (ref "D5") (pin "2") (pinfunction "2_2") (pintype "passive"))
      (node (ref "D6") (pin "2") (pinfunction "2_2") (pintype "passive"))
      (node (ref "D7") (pin "2") (pinfunction "2_2") (pintype "passive"))
      (node (ref "D8") (pin "2") (pinfunction "2_2") (pintype "passive"))
      (node (ref "J1") (pin "1") (pinfunction "1_1") (pintype "passive"))
      (node (ref "J1") (pin "M1") (pinfunction "M1_M1") (pintype "passive"))
      (node (ref "J1") (pin "M2") (pinfunction "M2_M2") (pintype "passive"))
      (node (ref "R10") (pin "1") (pinfunction "1_1") (pintype "passive"))
      (node (ref "R20") (pin "1") (pinfunction "1_1") (pintype "passive"))
      (node (ref "R22") (pin "2") (pinfunction "2_2") (pintype "passive"))
      (node (ref "R23") (pin "1") (pinfunction "1_1") (pintype "passive"))
      (node (ref "R24") (pin "2") (pinfunction "2_2") (pintype "passive"))
      (node (ref "R25") (pin "1") (pinfunction "1_1") (pintype "passive"))
      (node (ref "R26") (pin "1") (pinfunction "1_1") (pintype "passive"))
      (node (ref "R32") (pin "2") (pinfunction "2_2") (pintype "passive"))
      (node (ref "R34") (pin "1") (pinfunction "1_1") (pintype "passive"))
      (node (ref "R356") (pin "1") (pinfunction "1_1") (pintype "passive"))
      (node (ref "R39") (pin "1") (pinfunction "1_1") (pintype "passive"))
      (node (ref "R40") (pin "2") (pinfunction "2_2") (pintype "passive"))
      (node (ref "R41") (pin "1") (pinfunction "1_1") (pintype "passive"))
      (node (ref "R42") (pin "1") (pinfunction "1_1") (pintype "passive"))
      (node (ref "R48") (pin "2") (pinfunction "2_2") (pintype "passive"))
      (node (ref "R49") (pin "1") (pinfunction "1_1") (pintype "passive"))
      (node (ref "R52") (pin "1") (pinfunction "1_1") (pintype "passive"))
      (node (ref "R53") (pin "1") (pinfunction "1_1") (pintype "passive"))
      (node (ref "R54") (pin "1") (pinfunction "1_1") (pintype "passive"))
      (node (ref "R56") (pin "1") (pinfunction "1_1") (pintype "passive"))
      (node (ref "R7") (pin "1") (pinfunction "1_1") (pintype "passive"))
      (node (ref "R8") (pin "1") (pinfunction "1_1") (pintype "passive"))
      (node (ref "R9") (pin "1") (pinfunction "1_1") (pintype "passive"))
      (node (ref "U1") (pin "6") (pinfunction "GND_6") (pintype "power_in"))
      (node (ref "U1") (pin "9") (pinfunction "PAD_9") (pintype "power_in"))
      (node (ref "U2") (pin "8") (pinfunction "8_8") (pintype "passive"))
      (node (ref "U3") (pin "8") (pinfunction "8_8") (pintype "passive"))
      (node (ref "U4") (pin "8") (pinfunction "8_8") (pintype "passive"))
      (node (ref "U5") (pin "8") (pinfunction "8_8") (pintype "passive"))
      (node (ref "U6") (pin "8") (pinfunction "8_8") (pintype "passive"))
      (node (ref "U7") (pin "8") (pinfunction "8_8") (pintype "passive"))
      (node (ref "U8") (pin "6") (pinfunction "GND_6") (pintype "power_in"))
      (node (ref "U8") (pin "9") (pinfunction "PAD_9") (pintype "power_in"))
      (node (ref "U9") (pin "2") (pinfunction "GND_2") (pintype "passive"))
      (node (ref "VR1") (pin "1") (pinfunction "GND_1") (pintype "power_in"))
    )
    (net (code "13") (name "Net-(C8-Pad2)") (class "Default")
      (node (ref "C8") (pin "2") (pinfunction "2_2") (pintype "passive"))
      (node (ref "U2") (pin "10") (pinfunction "10_10") (pintype "passive"))
    )
    (net (code "14") (name "Net-(C9-Pad2)") (class "Default")
      (node (ref "C9") (pin "2") (pinfunction "2_2") (pintype "passive"))
      (node (ref "U2") (pin "7") (pinfunction "7_7") (pintype "passive"))
    )
    (net (code "15") (name "Net-(C14-Pad2)") (class "Default")
      (node (ref "C14") (pin "2") (pinfunction "2_2") (pintype "passive"))
      (node (ref "U3") (pin "10") (pinfunction "10_10") (pintype "passive"))
    )
    (net (code "16") (name "Net-(C15-Pad2)") (class "Default")
      (node (ref "C15") (pin "2") (pinfunction "2_2") (pintype "passive"))
      (node (ref "U3") (pin "7") (pinfunction "7_7") (pintype "passive"))
    )
    (net (code "17") (name "Net-(C16-Pad2)") (class "Default")
      (node (ref "C16") (pin "2") (pinfunction "2_2") (pintype "passive"))
      (node (ref "U4") (pin "10") (pinfunction "10_10") (pintype "passive"))
    )
    (net (code "18") (name "Net-(C17-Pad2)") (class "Default")
      (node (ref "C17") (pin "2") (pinfunction "2_2") (pintype "passive"))
      (node (ref "U4") (pin "7") (pinfunction "7_7") (pintype "passive"))
    )
    (net (code "19") (name "Net-(C22-Pad2)") (class "Default")
      (node (ref "C22") (pin "2") (pinfunction "2_2") (pintype "passive"))
      (node (ref "U5") (pin "10") (pinfunction "10_10") (pintype "passive"))
    )
    (net (code "20") (name "Net-(C23-Pad2)") (class "Default")
      (node (ref "C23") (pin "2") (pinfunction "2_2") (pintype "passive"))
      (node (ref "U5") (pin "7") (pinfunction "7_7") (pintype "passive"))
    )
    (net (code "21") (name "Net-(C24-Pad2)") (class "Default")
      (node (ref "C24") (pin "2") (pinfunction "2_2") (pintype "passive"))
      (node (ref "U6") (pin "10") (pinfunction "10_10") (pintype "passive"))
    )
    (net (code "22") (name "Net-(C25-Pad2)") (class "Default")
      (node (ref "C25") (pin "2") (pinfunction "2_2") (pintype "passive"))
      (node (ref "U6") (pin "7") (pinfunction "7_7") (pintype "passive"))
    )
    (net (code "23") (name "Net-(C33-Pad2)") (class "Default")
      (node (ref "C33") (pin "2") (pinfunction "2_2") (pintype "passive"))
      (node (ref "U7") (pin "10") (pinfunction "10_10") (pintype "passive"))
    )
    (net (code "24") (name "Net-(C34-Pad2)") (class "Default")
      (node (ref "C34") (pin "2") (pinfunction "2_2") (pintype "passive"))
      (node (ref "U7") (pin "7") (pinfunction "7_7") (pintype "passive"))
    )
    (net (code "25") (name "Net-(D1-K)") (class "Default")
      (node (ref "D1") (pin "1") (pinfunction "K_1") (pintype "passive"))
      (node (ref "R9") (pin "2") (pinfunction "2_2") (pintype "passive"))
    )
    (net (code "26") (name "Net-(D9-K)") (class "Default")
      (node (ref "D9") (pin "1") (pinfunction "K_1") (pintype "passive"))
      (node (ref "R54") (pin "2") (pinfunction "2_2") (pintype "passive"))
    )
    (net (code "27") (name "Net-(D11-K)") (class "Default")
      (node (ref "D11") (pin "1") (pinfunction "K_1") (pintype "passive"))
      (node (ref "R56") (pin "2") (pinfunction "2_2") (pintype "passive"))
    )
    (net (code "28") (name "Net-(D36-K)") (class "Default")
      (node (ref "D36") (pin "1") (pinfunction "K_1") (pintype "passive"))
      (node (ref "R356") (pin "2") (pinfunction "2_2") (pintype "passive"))
    )
    (net (code "29") (name "Net-(U1-BOOT)") (class "Default")
      (node (ref "C1") (pin "2") (pinfunction "2_2") (pintype "passive"))
      (node (ref "U1") (pin "1") (pinfunction "BOOT_1") (pintype "power_in"))
    )
    (net (code "30") (name "Net-(U1-ENA)") (class "Default")
      (node (ref "R2") (pin "1") (pinfunction "1_1") (pintype "passive"))
      (node (ref "U1") (pin "5") (pinfunction "ENA_5") (pintype "input"))
    )
    (net (code "31") (name "Net-(U1-PH)") (class "Default")
      (node (ref "C1") (pin "1") (pinfunction "1_1") (pintype "passive"))
      (node (ref "D3") (pin "1") (pinfunction "1_1") (pintype "passive"))
      (node (ref "L1") (pin "1") (pinfunction "1_1") (pintype "passive"))
      (node (ref "U1") (pin "8") (pinfunction "PH_8") (pintype "power_in"))
    )
    (net (code "32") (name "Net-(U1-VSENSE)") (class "Default")
      (node (ref "R3") (pin "1") (pinfunction "1_1") (pintype "passive"))
      (node (ref "R8") (pin "2") (pinfunction "2_2") (pintype "passive"))
      (node (ref "U1") (pin "4") (pinfunction "VSENSE_4") (pintype "input"))
    )
    (net (code "33") (name "Net-(U2-EN{slash}UVLO)") (class "Default")
      (node (ref "R1") (pin "1") (pinfunction "1_1") (pintype "passive"))
      (node (ref "R6") (pin "2") (pinfunction "2_2") (pintype "passive"))
      (node (ref "U2") (pin "1") (pinfunction "EN/UVLO_1") (pintype "passive"))
    )
    (net (code "34") (name "Net-(U2-OVLO{slash}OVCSEL)") (class "Default")
      (node (ref "R6") (pin "1") (pinfunction "1_1") (pintype "passive"))
      (node (ref "R7") (pin "2") (pinfunction "2_2") (pintype "passive"))
      (node (ref "U2") (pin "2") (pinfunction "OVLO/OVCSEL_2") (pintype "passive"))
    )
    (net (code "35") (name "Net-(U2-PGTH{slash}~{FLT})") (class "Default")
      (node (ref "R5") (pin "1") (pinfunction "1_1") (pintype "passive"))
      (node (ref "U2") (pin "4") (pinfunction "PGTH/~{FLT}_4") (pintype "passive"))
    )
    (net (code "36") (name "Net-(U2-PG{slash}AUXOFF)") (class "Default")
      (node (ref "R4") (pin "1") (pinfunction "1_1") (pintype "passive"))
      (node (ref "U2") (pin "3") (pinfunction "PG/AUXOFF_3") (pintype "passive"))
    )
    (net (code "37") (name "Net-(U3-EN{slash}UVLO)") (class "Default")
      (node (ref "R15") (pin "1") (pinfunction "1_1") (pintype "passive"))
      (node (ref "R19") (pin "1") (pinfunction "1_1") (pintype "passive"))
      (node (ref "R22") (pin "1") (pinfunction "1_1") (pintype "passive"))
      (node (ref "U3") (pin "1") (pinfunction "EN/UVLO_1") (pintype "passive"))
    )
    (net (code "38") (name "Net-(U3-OVLO{slash}OVCSEL)") (class "Default")
      (node (ref "R11") (pin "1") (pinfunction "1_1") (pintype "passive"))
      (node (ref "R20") (pin "2") (pinfunction "2_2") (pintype "passive"))
      (node (ref "U3") (pin "2") (pinfunction "OVLO/OVCSEL_2") (pintype "passive"))
    )
    (net (code "39") (name "Net-(U3-PGTH{slash}~{FLT})") (class "Default")
      (node (ref "R13") (pin "1") (pinfunction "1_1") (pintype "passive"))
      (node (ref "U3") (pin "4") (pinfunction "PGTH/~{FLT}_4") (pintype "passive"))
    )
    (net (code "40") (name "Net-(U3-PG{slash}AUXOFF)") (class "Default")
      (node (ref "R12") (pin "1") (pinfunction "1_1") (pintype "passive"))
      (node (ref "U3") (pin "3") (pinfunction "PG/AUXOFF_3") (pintype "passive"))
    )
    (net (code "41") (name "Net-(U4-EN{slash}UVLO)") (class "Default")
      (node (ref "R18") (pin "1") (pinfunction "1_1") (pintype "passive"))
      (node (ref "R21") (pin "1") (pinfunction "1_1") (pintype "passive"))
      (node (ref "R24") (pin "1") (pinfunction "1_1") (pintype "passive"))
      (node (ref "U4") (pin "1") (pinfunction "EN/UVLO_1") (pintype "passive"))
    )
    (net (code "42") (name "Net-(U4-OVLO{slash}OVCSEL)") (class "Default")
      (node (ref "R14") (pin "1") (pinfunction "1_1") (pintype "passive"))
      (node (ref "R23") (pin "2") (pinfunction "2_2") (pintype "passive"))
      (node (ref "U4") (pin "2") (pinfunction "OVLO/OVCSEL_2") (pintype "passive"))
    )
    (net (code "43") (name "Net-(U4-PGTH{slash}~{FLT})") (class "Default")
      (node (ref "R17") (pin "1") (pinfunction "1_1") (pintype "passive"))
      (node (ref "U4") (pin "4") (pinfunction "PGTH/~{FLT}_4") (pintype "passive"))
    )
    (net (code "44") (name "Net-(U4-PG{slash}AUXOFF)") (class "Default")
      (node (ref "R16") (pin "1") (pinfunction "1_1") (pintype "passive"))
      (node (ref "U4") (pin "3") (pinfunction "PG/AUXOFF_3") (pintype "passive"))
    )
    (net (code "45") (name "Net-(U5-EN{slash}UVLO)") (class "Default")
      (node (ref "R27") (pin "1") (pinfunction "1_1") (pintype "passive"))
      (node (ref "R31") (pin "1") (pinfunction "1_1") (pintype "passive"))
      (node (ref "R32") (pin "1") (pinfunction "1_1") (pintype "passive"))
      (node (ref "U5") (pin "1") (pinfunction "EN/UVLO_1") (pintype "passive"))
    )
    (net (code "46") (name "Net-(U5-OVLO{slash}OVCSEL)") (class "Default")
      (node (ref "R28") (pin "1") (pinfunction "1_1") (pintype "passive"))
      (node (ref "R34") (pin "2") (pinfunction "2_2") (pintype "passive"))
      (node (ref "U5") (pin "2") (pinfunction "OVLO/OVCSEL_2") (pintype "passive"))
    )
    (net (code "47") (name "Net-(U5-PGTH{slash}~{FLT})") (class "Default")
      (node (ref "R30") (pin "1") (pinfunction "1_1") (pintype "passive"))
      (node (ref "U5") (pin "4") (pinfunction "PGTH/~{FLT}_4") (pintype "passive"))
    )
    (net (code "48") (name "Net-(U5-PG{slash}AUXOFF)") (class "Default")
      (node (ref "R29") (pin "1") (pinfunction "1_1") (pintype "passive"))
      (node (ref "U5") (pin "3") (pinfunction "PG/AUXOFF_3") (pintype "passive"))
    )
    (net (code "49") (name "Net-(U6-EN{slash}UVLO)") (class "Default")
      (node (ref "R37") (pin "1") (pinfunction "1_1") (pintype "passive"))
      (node (ref "R38") (pin "1") (pinfunction "1_1") (pintype "passive"))
      (node (ref "R40") (pin "1") (pinfunction "1_1") (pintype "passive"))
      (node (ref "U6") (pin "1") (pinfunction "EN/UVLO_1") (pintype "passive"))
    )
    (net (code "50") (name "Net-(U6-OVLO{slash}OVCSEL)") (class "Default")
      (node (ref "R33") (pin "1") (pinfunction "1_1") (pintype "passive"))
      (node (ref "R39") (pin "2") (pinfunction "2_2") (pintype "passive"))
      (node (ref "U6") (pin "2") (pinfunction "OVLO/OVCSEL_2") (pintype "passive"))
    )
    (net (code "51") (name "Net-(U6-PGTH{slash}~{FLT})") (class "Default")
      (node (ref "R36") (pin "1") (pinfunction "1_1") (pintype "passive"))
      (node (ref "U6") (pin "4") (pinfunction "PGTH/~{FLT}_4") (pintype "passive"))
    )
    (net (code "52") (name "Net-(U6-PG{slash}AUXOFF)") (class "Default")
      (node (ref "R35") (pin "1") (pinfunction "1_1") (pintype "passive"))
      (node (ref "U6") (pin "3") (pinfunction "PG/AUXOFF_3") (pintype "passive"))
    )
    (net (code "53") (name "Net-(U7-EN{slash}UVLO)") (class "Default")
      (node (ref "R43") (pin "1") (pinfunction "1_1") (pintype "passive"))
      (node (ref "R47") (pin "1") (pinfunction "1_1") (pintype "passive"))
      (node (ref "R48") (pin "1") (pinfunction "1_1") (pintype "passive"))
      (node (ref "U7") (pin "1") (pinfunction "EN/UVLO_1") (pintype "passive"))
    )
    (net (code "54") (name "Net-(U7-OVLO{slash}OVCSEL)") (class "Default")
      (node (ref "R44") (pin "1") (pinfunction "1_1") (pintype "passive"))
      (node (ref "R49") (pin "2") (pinfunction "2_2") (pintype "passive"))
      (node (ref "U7") (pin "2") (pinfunction "OVLO/OVCSEL_2") (pintype "passive"))
    )
    (net (code "55") (name "Net-(U7-PGTH{slash}~{FLT})") (class "Default")
      (node (ref "R46") (pin "1") (pinfunction "1_1") (pintype "passive"))
      (node (ref "U7") (pin "4") (pinfunction "PGTH/~{FLT}_4") (pintype "passive"))
    )
    (net (code "56") (name "Net-(U7-PG{slash}AUXOFF)") (class "Default")
      (node (ref "R45") (pin "1") (pinfunction "1_1") (pintype "passive"))
      (node (ref "U7") (pin "3") (pinfunction "PG/AUXOFF_3") (pintype "passive"))
    )
    (net (code "57") (name "Net-(U8-BOOT)") (class "Default")
      (node (ref "C28") (pin "2") (pinfunction "2_2") (pintype "passive"))
      (node (ref "U8") (pin "1") (pinfunction "BOOT_1") (pintype "power_in"))
    )
    (net (code "58") (name "Net-(U8-ENA)") (class "Default")
      (node (ref "R50") (pin "1") (pinfunction "1_1") (pintype "passive"))
      (node (ref "U8") (pin "5") (pinfunction "ENA_5") (pintype "input"))
    )
    (net (code "59") (name "Net-(U8-PH)") (class "Default")
      (node (ref "C28") (pin "1") (pinfunction "1_1") (pintype "passive"))
      (node (ref "D10") (pin "1") (pinfunction "1_1") (pintype "passive"))
      (node (ref "L2") (pin "1") (pinfunction "1_1") (pintype "passive"))
      (node (ref "U8") (pin "8") (pinfunction "PH_8") (pintype "power_in"))
    )
    (net (code "60") (name "Net-(U8-VSENSE)") (class "Default")
      (node (ref "R51") (pin "1") (pinfunction "1_1") (pintype "passive"))
      (node (ref "R53") (pin "2") (pinfunction "2_2") (pintype "passive"))
      (node (ref "U8") (pin "4") (pinfunction "VSENSE_4") (pintype "input"))
    )
    (net (code "61") (name "Net-(U9-EN)") (class "Default")
      (node (ref "R55") (pin "1") (pinfunction "1_1") (pintype "passive"))
      (node (ref "U9") (pin "3") (pinfunction "EN_3") (pintype "passive"))
    )
    (net (code "62") (name "POW_ONOFF_HD4") (class "Default")
      (node (ref "R31") (pin "2") (pinfunction "2_2") (pintype "passive"))
    )
    (net (code "63") (name "POW_ONOFF_Heater") (class "Default")
      (node (ref "R18") (pin "2") (pinfunction "2_2") (pintype "passive"))
    )
    (net (code "64") (name "POW_ONOFF_IO") (class "Default")
      (node (ref "R15") (pin "2") (pinfunction "2_2") (pintype "passive"))
    )
    (net (code "65") (name "POW_ONOFF_Solenoid") (class "Default")
      (node (ref "R37") (pin "2") (pinfunction "2_2") (pintype "passive"))
    )
    (net (code "66") (name "POW_ONOFF_TEC") (class "Default")
      (node (ref "R47") (pin "2") (pinfunction "2_2") (pintype "passive"))
    )
    (net (code "67") (name "eFUSE_ILIM_5V_HD4") (class "Default")
      (node (ref "R41") (pin "2") (pinfunction "2_2") (pintype "passive"))
      (node (ref "U5") (pin "9") (pinfunction "9_9") (pintype "passive"))
    )
    (net (code "68") (name "eFUSE_ILIM_5V_IO") (class "Default")
      (node (ref "R25") (pin "2") (pinfunction "2_2") (pintype "passive"))
      (node (ref "U3") (pin "9") (pinfunction "9_9") (pintype "passive"))
    )
    (net (code "69") (name "eFUSE_ILIM_5V_TEC") (class "Default")
      (node (ref "R52") (pin "2") (pinfunction "2_2") (pintype "passive"))
      (node (ref "U7") (pin "9") (pinfunction "9_9") (pintype "passive"))
    )
    (net (code "70") (name "eFUSE_ILIM_12V") (class "Default")
      (node (ref "R10") (pin "2") (pinfunction "2_2") (pintype "passive"))
      (node (ref "U2") (pin "9") (pinfunction "9_9") (pintype "passive"))
    )
    (net (code "71") (name "eFUSE_ILIM_12V_Heater") (class "Default")
      (node (ref "R26") (pin "2") (pinfunction "2_2") (pintype "passive"))
      (node (ref "U4") (pin "9") (pinfunction "9_9") (pintype "passive"))
    )
    (net (code "72") (name "eFUSE_ILIM_12V_Solenoid") (class "Default")
      (node (ref "R42") (pin "2") (pinfunction "2_2") (pintype "passive"))
      (node (ref "U6") (pin "9") (pinfunction "9_9") (pintype "passive"))
    )
    (net (code "73") (name "unconnected-(U1-NC-Pad2)") (class "Default")
      (node (ref "U1") (pin "2") (pinfunction "NC_2") (pintype "passive"))
    )
    (net (code "74") (name "unconnected-(U1-NC-Pad3)") (class "Default")
      (node (ref "U1") (pin "3") (pinfunction "NC_3") (pintype "passive"))
    )
    (net (code "75") (name "unconnected-(U8-NC-Pad2)") (class "Default")
      (node (ref "U8") (pin "2") (pinfunction "NC_2") (pintype "passive"))
    )
    (net (code "76") (name "unconnected-(U8-NC-Pad3)") (class "Default")
      (node (ref "U8") (pin "3") (pinfunction "NC_3") (pintype "passive"))
    )
    (net (code "77") (name "unconnected-(U9-NC-Pad4)") (class "Default")
      (node (ref "U9") (pin "4") (pinfunction "NC_4") (pintype "passive+no_connect"))
    )
  )
)
